# Teeny.net
KiCad netlist of a schematic drawn in Altium Designer
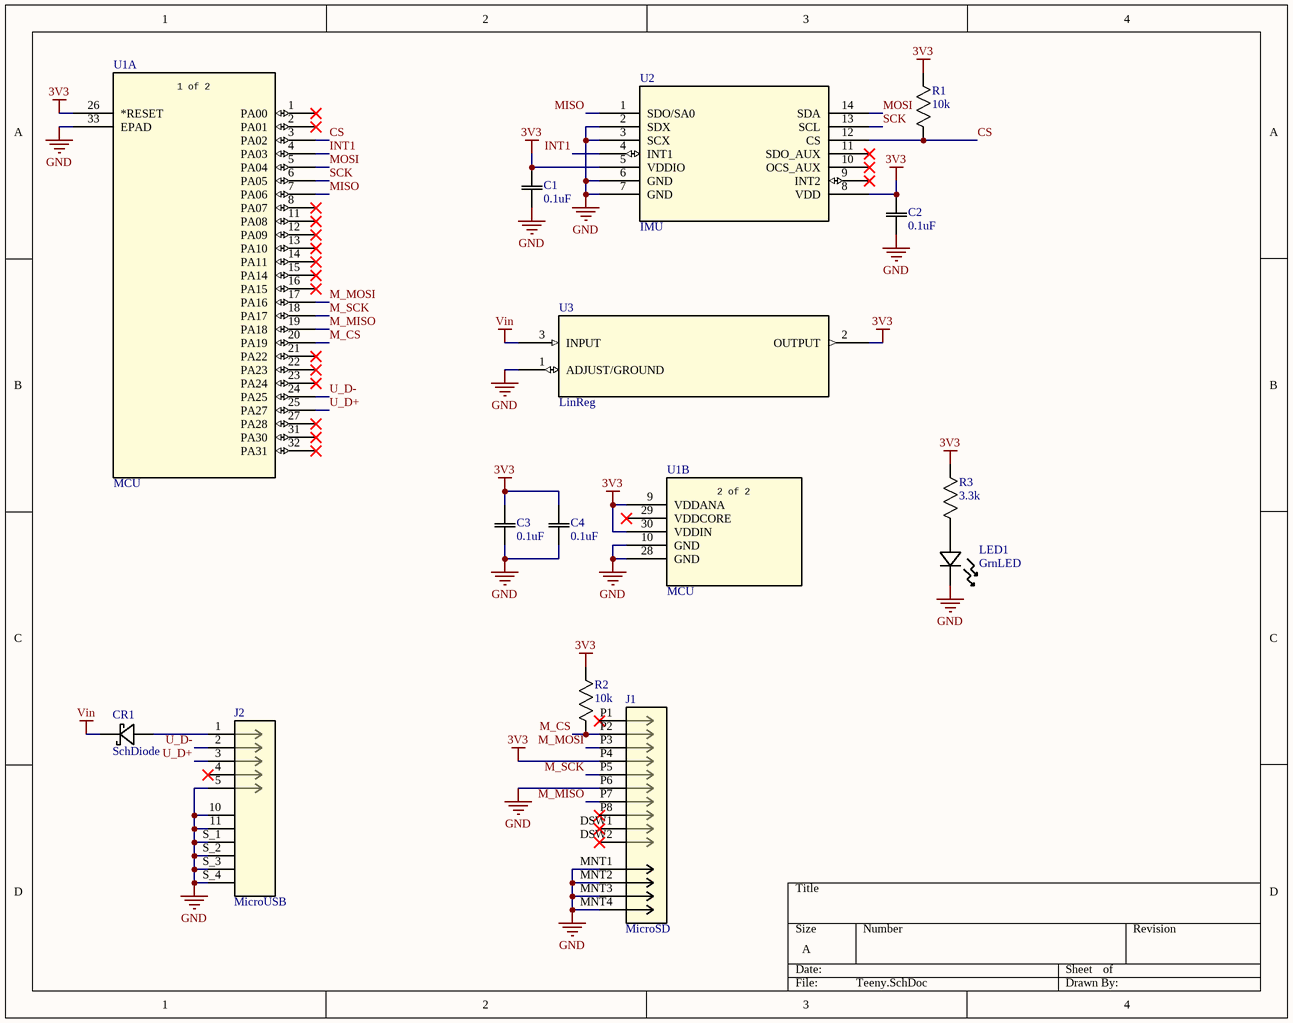
[diagram p0: Teeny.SchDoc]

(export (version "E")
  (design (tool "Eeschema 10.0.6"))
  (components
    (comp (ref "C1")
      (value "0.1uF")
      (footprint "0.1uF/16V")
      (description "GRM155R71C104KA88D")
      (fields (field (name "COPYRIGHT") "Copyright (C) 2026 Ultra Librarian. All rights reserved."))
      (libsource (lib "Teeny") (part "0.1uF/16V"))
    )
    (comp (ref "C2")
      (value "0.1uF")
      (footprint "0.1uF/16V")
      (description "GRM155R71C104KA88D")
      (fields (field (name "COPYRIGHT") "Copyright (C) 2026 Ultra Librarian. All rights reserved."))
      (libsource (lib "Teeny") (part "0.1uF/16V"))
    )
    (comp (ref "C3")
      (value "0.1uF")
      (footprint "0.1uF/16V")
      (description "GRM155R71C104KA88D")
      (fields (field (name "COPYRIGHT") "Copyright (C) 2026 Ultra Librarian. All rights reserved."))
      (libsource (lib "Teeny") (part "0.1uF/16V"))
    )
    (comp (ref "C4")
      (value "0.1uF")
      (footprint "0.1uF/16V")
      (description "GRM155R71C104KA88D")
      (fields (field (name "COPYRIGHT") "Copyright (C) 2026 Ultra Librarian. All rights reserved."))
      (libsource (lib "Teeny") (part "0.1uF/16V"))
    )
    (comp (ref "CR1")
      (value "SchDiode")
      (footprint "SchDiode")
      (description "B5819W-TP")
      (fields (field (name "COPYRIGHT") "Copyright (C) 2025 Ultra Librarian. All rights reserved."))
      (libsource (lib "Teeny") (part "Schottky Diode"))
    )
    (comp (ref "J1")
      (value "MicroSD")
      (footprint "MicroSD")
      (description "MEM2080-00-128-00-A")
      (fields (field (name "COPYRIGHT") "Copyright (C) 2025 Ultra Librarian. All rights reserved."))
      (libsource (lib "Teeny") (part "MicroSD"))
    )
    (comp (ref "J2")
      (value "MicroUSB")
      (footprint "MicroUSB")
      (description "10118194-0001LF")
      (fields (field (name "COPYRIGHT") "Copyright (C) 2026 Ultra Librarian. All rights reserved."))
      (libsource (lib "Teeny") (part "MicroUSB"))
    )
    (comp (ref "LED1")
      (value "GrnLED")
      (footprint "GreenLED")
      (description "LTST-C190KGKT")
      (fields (field (name "COPYRIGHT") "Copyright (C) 2025 Ultra Librarian. All rights reserved."))
      (libsource (lib "Teeny") (part "GreenLED"))
    )
    (comp (ref "R1")
      (value "10k")
      (footprint "10k/0.05W")
      (description "RC0201FR-0710KL")
      (fields (field (name "COPYRIGHT") "Copyright (C) 2025 Ultra Librarian. All rights reserved."))
      (libsource (lib "Teeny") (part "10k/0.05W"))
    )
    (comp (ref "R2")
      (value "10k")
      (footprint "10k/0.05W")
      (description "RC0201FR-0710KL")
      (fields (field (name "COPYRIGHT") "Copyright (C) 2025 Ultra Librarian. All rights reserved."))
      (libsource (lib "Teeny") (part "10k/0.05W"))
    )
    (comp (ref "R3")
      (value "3.3k")
      (footprint "3.3k/0.1W")
      (description "RC0603FR-073K3L")
      (fields (field (name "COPYRIGHT") "Copyright (C) 2025 Ultra Librarian. All rights reserved."))
      (libsource (lib "Teeny") (part "3.3k/0.1W"))
    )
    (comp (ref "U1")
      (value "MCU")
      (footprint "MCU")
      (description "ATSAMD21E18A-MUT")
      (fields (field (name "COPYRIGHT") "Copyright (C) 2026 Ultra Librarian. All rights reserved."))
      (libsource (lib "Teeny") (part "MCU"))
    )
    (comp (ref "U2")
      (value "IMU")
      (footprint "IMU")
      (description "LSM6DSRXTR")
      (fields (field (name "COPYRIGHT") "Copyright (C) 2025 Ultra Librarian. All rights reserved."))
      (libsource (lib "Teeny") (part "IMU"))
    )
    (comp (ref "U3")
      (value "LinReg")
      (footprint "LinReg")
      (description "NCP1117ST33T3G")
      (fields (field (name "COPYRIGHT") "Copyright (C) 2026 Ultra Librarian. All rights reserved."))
      (libsource (lib "Teeny") (part "LinReg"))
    )
  )
  (nets
    (net (code "1") (name "/CS") (class "Default")
      (node (ref "R1") (pin "1") (pinfunction "1_1") (pintype "passive"))
      (node (ref "U1") (pin "3") (pinfunction "PA02_3") (pintype "bidirectional"))
      (node (ref "U2") (pin "12") (pinfunction "CS_12") (pintype "passive"))
    )
    (net (code "2") (name "/INT1") (class "Default")
      (node (ref "U1") (pin "4") (pinfunction "PA03_4") (pintype "bidirectional"))
      (node (ref "U2") (pin "4") (pinfunction "INT1_4") (pintype "bidirectional"))
    )
    (net (code "3") (name "/MISO") (class "Default")
      (node (ref "U1") (pin "7") (pinfunction "PA06_7") (pintype "bidirectional"))
      (node (ref "U2") (pin "1") (pinfunction "SDO/SA0_1") (pintype "passive"))
    )
    (net (code "4") (name "/MOSI") (class "Default")
      (node (ref "U1") (pin "5") (pinfunction "PA04_5") (pintype "bidirectional"))
      (node (ref "U2") (pin "14") (pinfunction "SDA_14") (pintype "passive"))
    )
    (net (code "5") (name "/M_CS") (class "Default")
      (node (ref "J1") (pin "P2") (pinfunction "CD/DAT3_P2") (pintype "passive"))
      (node (ref "R2") (pin "1") (pinfunction "1_1") (pintype "passive"))
      (node (ref "U1") (pin "20") (pinfunction "PA19_20") (pintype "bidirectional"))
    )
    (net (code "6") (name "/M_MISO") (class "Default")
      (node (ref "J1") (pin "P7") (pinfunction "DAT0_P7") (pintype "passive"))
      (node (ref "U1") (pin "19") (pinfunction "PA18_19") (pintype "bidirectional"))
    )
    (net (code "7") (name "/M_MOSI") (class "Default")
      (node (ref "J1") (pin "P3") (pinfunction "CMD_P3") (pintype "passive"))
      (node (ref "U1") (pin "17") (pinfunction "PA16_17") (pintype "bidirectional"))
    )
    (net (code "8") (name "/M_SCK") (class "Default")
      (node (ref "J1") (pin "P5") (pinfunction "CLK_P5") (pintype "passive"))
      (node (ref "U1") (pin "18") (pinfunction "PA17_18") (pintype "bidirectional"))
    )
    (net (code "9") (name "/SCK") (class "Default")
      (node (ref "U1") (pin "6") (pinfunction "PA05_6") (pintype "bidirectional"))
      (node (ref "U2") (pin "13") (pinfunction "SCL_13") (pintype "passive"))
    )
    (net (code "10") (name "/U_D+") (class "Default")
      (node (ref "J2") (pin "3") (pinfunction "3_3") (pintype "passive"))
      (node (ref "U1") (pin "25") (pinfunction "PA27_25") (pintype "bidirectional"))
    )
    (net (code "11") (name "/U_D-") (class "Default")
      (node (ref "J2") (pin "2") (pinfunction "2_2") (pintype "passive"))
      (node (ref "U1") (pin "24") (pinfunction "PA25_24") (pintype "bidirectional"))
    )
    (net (code "12") (name "3V3") (class "Default")
      (node (ref "C1") (pin "2") (pinfunction "2_2") (pintype "passive"))
      (node (ref "C2") (pin "2") (pinfunction "2_2") (pintype "passive"))
      (node (ref "C3") (pin "2") (pinfunction "2_2") (pintype "passive"))
      (node (ref "C4") (pin "2") (pinfunction "2_2") (pintype "passive"))
      (node (ref "J1") (pin "P4") (pinfunction "VDD_P4") (pintype "passive"))
      (node (ref "R1") (pin "2") (pinfunction "2_2") (pintype "passive"))
      (node (ref "R2") (pin "2") (pinfunction "2_2") (pintype "passive"))
      (node (ref "R3") (pin "1") (pinfunction "1_1") (pintype "passive"))
      (node (ref "U1") (pin "26") (pinfunction "*RESET_26") (pintype "passive"))
      (node (ref "U1") (pin "30") (pinfunction "VDDIN_30") (pintype "power_in"))
      (node (ref "U1") (pin "9") (pinfunction "VDDANA_9") (pintype "power_in"))
      (node (ref "U2") (pin "5") (pinfunction "VDDIO_5") (pintype "power_in"))
      (node (ref "U2") (pin "8") (pinfunction "VDD_8") (pintype "power_in"))
      (node (ref "U3") (pin "2") (pinfunction "OUTPUT_2") (pintype "output"))
    )
    (net (code "13") (name "GND") (class "Default")
      (node (ref "C1") (pin "1") (pinfunction "1_1") (pintype "passive"))
      (node (ref "C2") (pin "1") (pinfunction "1_1") (pintype "passive"))
      (node (ref "C3") (pin "1") (pinfunction "1_1") (pintype "passive"))
      (node (ref "C4") (pin "1") (pinfunction "1_1") (pintype "passive"))
      (node (ref "J1") (pin "MNT1") (pinfunction "Mount_MNT1") (pintype "passive"))
      (node (ref "J1") (pin "MNT2") (pinfunction "Mount_MNT2") (pintype "passive"))
      (node (ref "J1") (pin "MNT3") (pinfunction "Mount_MNT3") (pintype "passive"))
      (node (ref "J1") (pin "MNT4") (pinfunction "Mount_MNT4") (pintype "passive"))
      (node (ref "J1") (pin "P6") (pinfunction "VSS_P6") (pintype "passive"))
      (node (ref "J2") (pin "10") (pinfunction "10_10") (pintype "passive"))
      (node (ref "J2") (pin "11") (pinfunction "11_11") (pintype "passive"))
      (node (ref "J2") (pin "5") (pinfunction "5_5") (pintype "passive"))
      (node (ref "J2") (pin "S_1") (pinfunction "S_1_S_1") (pintype "passive"))
      (node (ref "J2") (pin "S_2") (pinfunction "S_2_S_2") (pintype "passive"))
      (node (ref "J2") (pin "S_3") (pinfunction "S_3_S_3") (pintype "passive"))
      (node (ref "J2") (pin "S_4") (pinfunction "S_4_S_4") (pintype "passive"))
      (node (ref "LED1") (pin "1") (pinfunction "1_1") (pintype "passive"))
      (node (ref "U1") (pin "10") (pinfunction "GND_10") (pintype "power_in"))
      (node (ref "U1") (pin "28") (pinfunction "GND_28") (pintype "power_in"))
      (node (ref "U1") (pin "33") (pinfunction "EPAD_33") (pintype "passive"))
      (node (ref "U2") (pin "2") (pinfunction "SDX_2") (pintype "passive"))
      (node (ref "U2") (pin "3") (pinfunction "SCX_3") (pintype "passive"))
      (node (ref "U2") (pin "6") (pinfunction "GND_6") (pintype "power_in"))
      (node (ref "U2") (pin "7") (pinfunction "GND_7") (pintype "power_in"))
      (node (ref "U3") (pin "1") (pinfunction "ADJUST/GROUND_1") (pintype "bidirectional"))
    )
    (net (code "14") (name "Net-(CR1-Pad2)") (class "Default")
      (node (ref "CR1") (pin "2") (pinfunction "2_2") (pintype "passive"))
      (node (ref "J2") (pin "1") (pinfunction "1_1") (pintype "passive"))
    )
    (net (code "15") (name "Net-(LED1-Pad2)") (class "Default")
      (node (ref "LED1") (pin "2") (pinfunction "2_2") (pintype "passive"))
      (node (ref "R3") (pin "2") (pinfunction "2_2") (pintype "passive"))
    )
    (net (code "16") (name "Vin") (class "Default")
      (node (ref "CR1") (pin "1") (pinfunction "1_1") (pintype "passive"))
      (node (ref "U3") (pin "3") (pinfunction "INPUT_3") (pintype "input"))
    )
    (net (code "17") (name "unconnected-(J1-DAT1-PadP8)") (class "Default")
      (node (ref "J1") (pin "P8") (pinfunction "DAT1_P8") (pintype "passive+no_connect"))
    )
    (net (code "18") (name "unconnected-(J1-DAT2-PadP1)") (class "Default")
      (node (ref "J1") (pin "P1") (pinfunction "DAT2_P1") (pintype "passive+no_connect"))
    )
    (net (code "19") (name "unconnected-(J1-LEVER-PadDSW1)") (class "Default")
      (node (ref "J1") (pin "DSW1") (pinfunction "LEVER_DSW1") (pintype "passive+no_connect"))
    )
    (net (code "20") (name "unconnected-(J1-SWITCH-PadDSW2)") (class "Default")
      (node (ref "J1") (pin "DSW2") (pinfunction "SWITCH_DSW2") (pintype "passive+no_connect"))
    )
    (net (code "21") (name "unconnected-(J2-Pad4)") (class "Default")
      (node (ref "J2") (pin "4") (pinfunction "4_4") (pintype "passive+no_connect"))
    )
    (net (code "22") (name "unconnected-(U1A-PA00-Pad1)") (class "Default")
      (node (ref "U1") (pin "1") (pinfunction "PA00_1") (pintype "bidirectional+no_connect"))
    )
    (net (code "23") (name "unconnected-(U1A-PA01-Pad2)") (class "Default")
      (node (ref "U1") (pin "2") (pinfunction "PA01_2") (pintype "bidirectional+no_connect"))
    )
    (net (code "24") (name "unconnected-(U1A-PA07-Pad8)") (class "Default")
      (node (ref "U1") (pin "8") (pinfunction "PA07_8") (pintype "bidirectional+no_connect"))
    )
    (net (code "25") (name "unconnected-(U1A-PA08-Pad11)") (class "Default")
      (node (ref "U1") (pin "11") (pinfunction "PA08_11") (pintype "bidirectional+no_connect"))
    )
    (net (code "26") (name "unconnected-(U1A-PA09-Pad12)") (class "Default")
      (node (ref "U1") (pin "12") (pinfunction "PA09_12") (pintype "bidirectional+no_connect"))
    )
    (net (code "27") (name "unconnected-(U1A-PA10-Pad13)") (class "Default")
      (node (ref "U1") (pin "13") (pinfunction "PA10_13") (pintype "bidirectional+no_connect"))
    )
    (net (code "28") (name "unconnected-(U1A-PA11-Pad14)") (class "Default")
      (node (ref "U1") (pin "14") (pinfunction "PA11_14") (pintype "bidirectional+no_connect"))
    )
    (net (code "29") (name "unconnected-(U1A-PA14-Pad15)") (class "Default")
      (node (ref "U1") (pin "15") (pinfunction "PA14_15") (pintype "bidirectional+no_connect"))
    )
    (net (code "30") (name "unconnected-(U1A-PA15-Pad16)") (class "Default")
      (node (ref "U1") (pin "16") (pinfunction "PA15_16") (pintype "bidirectional+no_connect"))
    )
    (net (code "31") (name "unconnected-(U1A-PA22-Pad21)") (class "Default")
      (node (ref "U1") (pin "21") (pinfunction "PA22_21") (pintype "bidirectional+no_connect"))
    )
    (net (code "32") (name "unconnected-(U1A-PA23-Pad22)") (class "Default")
      (node (ref "U1") (pin "22") (pinfunction "PA23_22") (pintype "bidirectional+no_connect"))
    )
    (net (code "33") (name "unconnected-(U1A-PA24-Pad23)") (class "Default")
      (node (ref "U1") (pin "23") (pinfunction "PA24_23") (pintype "bidirectional+no_connect"))
    )
    (net (code "34") (name "unconnected-(U1A-PA28-Pad27)") (class "Default")
      (node (ref "U1") (pin "27") (pinfunction "PA28_27") (pintype "bidirectional+no_connect"))
    )
    (net (code "35") (name "unconnected-(U1A-PA30-Pad31)") (class "Default")
      (node (ref "U1") (pin "31") (pinfunction "PA30_31") (pintype "bidirectional+no_connect"))
    )
    (net (code "36") (name "unconnected-(U1A-PA31-Pad32)") (class "Default")
      (node (ref "U1") (pin "32") (pinfunction "PA31_32") (pintype "bidirectional+no_connect"))
    )
    (net (code "37") (name "unconnected-(U1B-VDDCORE-Pad29)") (class "Default")
      (node (ref "U1") (pin "29") (pinfunction "VDDCORE_29") (pintype "power_in+no_connect"))
    )
    (net (code "38") (name "unconnected-(U2-INT2-Pad9)") (class "Default")
      (node (ref "U2") (pin "9") (pinfunction "INT2_9") (pintype "bidirectional+no_connect"))
    )
    (net (code "39") (name "unconnected-(U2-OCS_AUX-Pad10)") (class "Default")
      (node (ref "U2") (pin "10") (pinfunction "OCS_AUX_10") (pintype "passive+no_connect"))
    )
    (net (code "40") (name "unconnected-(U2-SDO_AUX-Pad11)") (class "Default")
      (node (ref "U2") (pin "11") (pinfunction "SDO_AUX_11") (pintype "passive+no_connect"))
    )
  )
)
